# OutputBoard.net
KiCad netlist of a schematic drawn in EAGLE
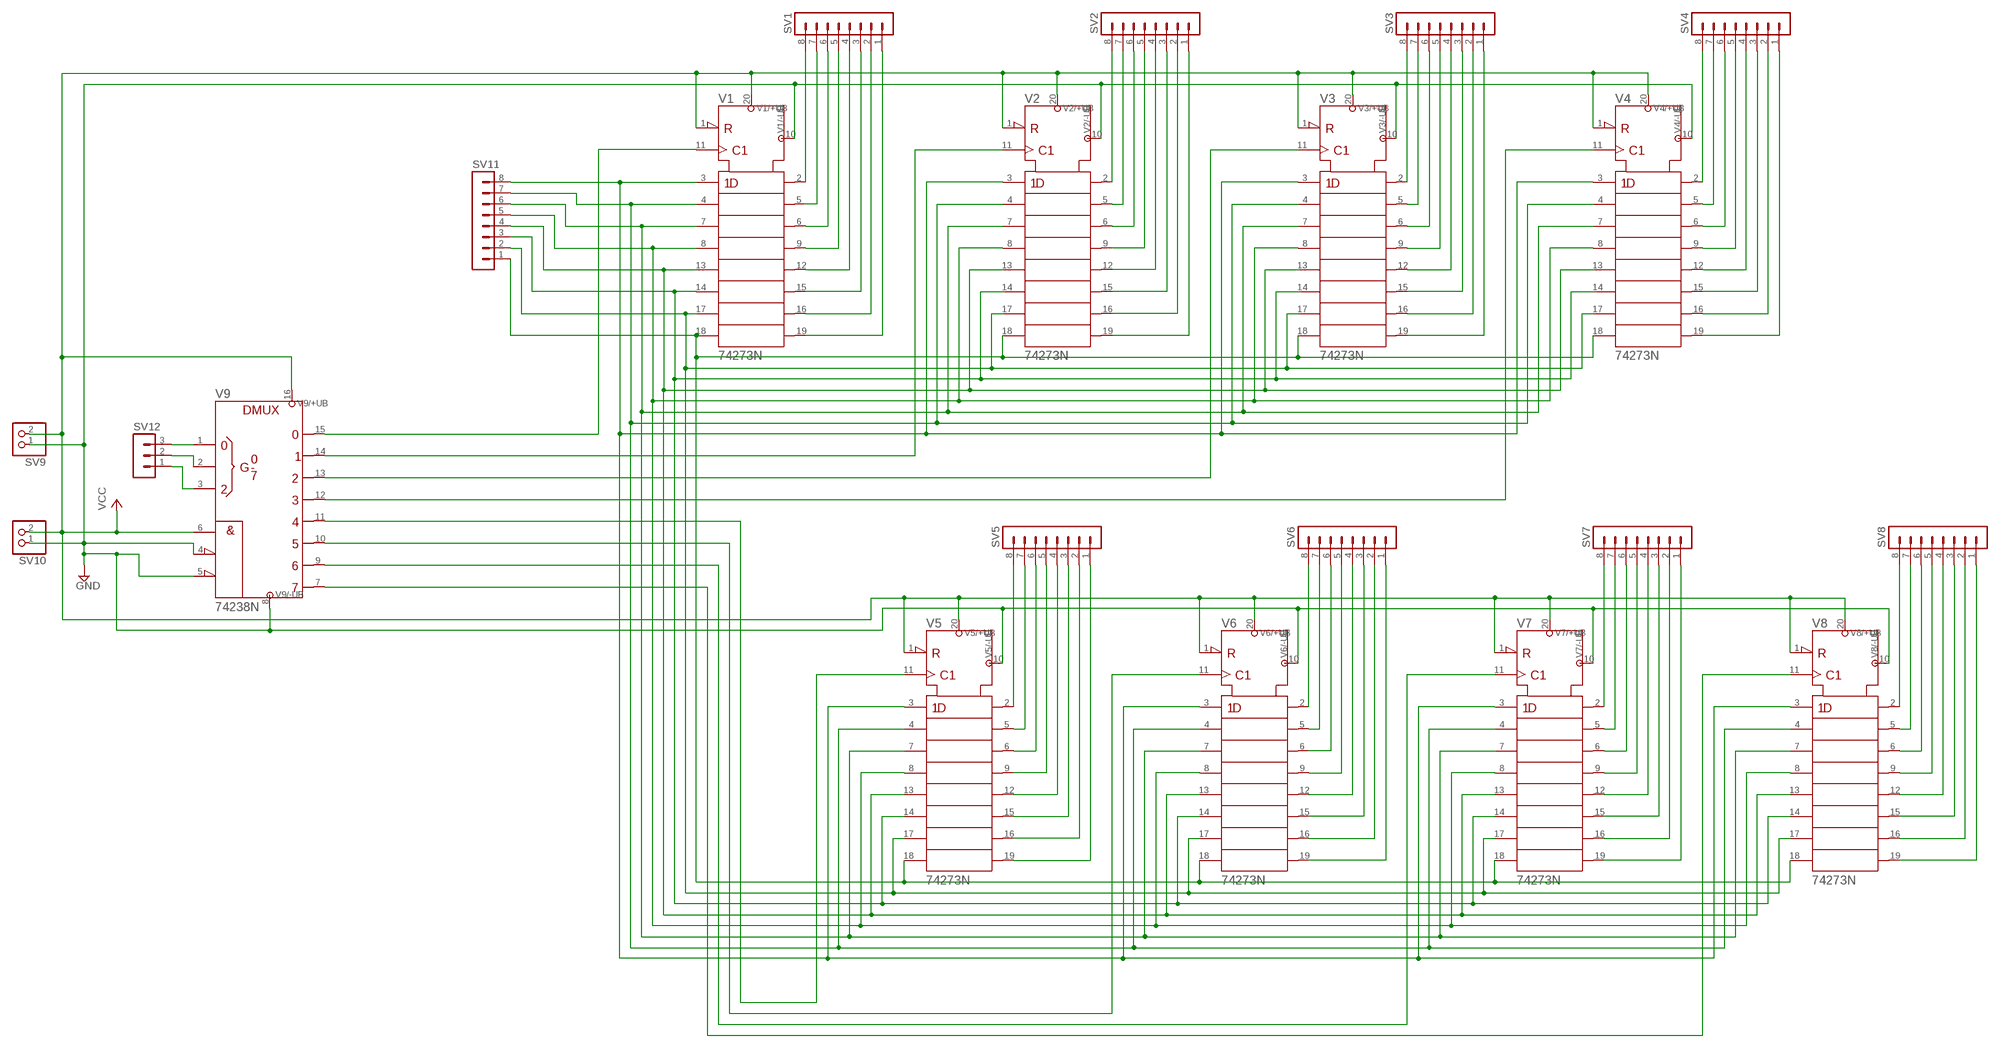
[diagram p0: schematic, sheet 1]

(export (version "E")
  (design (tool "Eeschema 10.0.6"))
  (components
    (comp (ref "SV1")
      (value "MA08-1")
      (footprint "eagle-import:MA08-1")
      (libsource (lib "eagle-import") (part "MA08-1"))
    )
    (comp (ref "SV2")
      (value "MA08-1")
      (footprint "eagle-import:MA08-1")
      (libsource (lib "eagle-import") (part "MA08-1"))
    )
    (comp (ref "SV3")
      (value "MA08-1")
      (footprint "eagle-import:MA08-1")
      (libsource (lib "eagle-import") (part "MA08-1"))
    )
    (comp (ref "SV4")
      (value "MA08-1")
      (footprint "eagle-import:MA08-1")
      (libsource (lib "eagle-import") (part "MA08-1"))
    )
    (comp (ref "SV5")
      (value "MA08-1")
      (footprint "eagle-import:MA08-1")
      (libsource (lib "eagle-import") (part "MA08-1"))
    )
    (comp (ref "SV6")
      (value "MA08-1")
      (footprint "eagle-import:MA08-1")
      (libsource (lib "eagle-import") (part "MA08-1"))
    )
    (comp (ref "SV7")
      (value "MA08-1")
      (footprint "eagle-import:MA08-1")
      (libsource (lib "eagle-import") (part "MA08-1"))
    )
    (comp (ref "SV8")
      (value "MA08-1")
      (footprint "eagle-import:MA08-1")
      (libsource (lib "eagle-import") (part "MA08-1"))
    )
    (comp (ref "SV9")
      (value "PINHD-1X2")
      (footprint "eagle-import:1X02")
      (libsource (lib "eagle-import") (part "PINHD-1X2"))
    )
    (comp (ref "SV10")
      (value "PINHD-1X2")
      (footprint "eagle-import:1X02")
      (libsource (lib "eagle-import") (part "PINHD-1X2"))
    )
    (comp (ref "SV11")
      (value "MA08-1")
      (footprint "eagle-import:MA08-1")
      (libsource (lib "eagle-import") (part "MA08-1"))
    )
    (comp (ref "SV12")
      (value "MA03-1")
      (footprint "eagle-import:MA03-1")
      (libsource (lib "eagle-import") (part "MA03-1"))
    )
    (comp (ref "V1")
      (value "74273N")
      (footprint "eagle-import:DIL20")
      (libsource (lib "eagle-import") (part "74273N"))
    )
    (comp (ref "V2")
      (value "74273N")
      (footprint "eagle-import:DIL20")
      (libsource (lib "eagle-import") (part "74273N"))
    )
    (comp (ref "V3")
      (value "74273N")
      (footprint "eagle-import:DIL20")
      (libsource (lib "eagle-import") (part "74273N"))
    )
    (comp (ref "V4")
      (value "74273N")
      (footprint "eagle-import:DIL20")
      (libsource (lib "eagle-import") (part "74273N"))
    )
    (comp (ref "V5")
      (value "74273N")
      (footprint "eagle-import:DIL20")
      (libsource (lib "eagle-import") (part "74273N"))
    )
    (comp (ref "V6")
      (value "74273N")
      (footprint "eagle-import:DIL20")
      (libsource (lib "eagle-import") (part "74273N"))
    )
    (comp (ref "V7")
      (value "74273N")
      (footprint "eagle-import:DIL20")
      (libsource (lib "eagle-import") (part "74273N"))
    )
    (comp (ref "V8")
      (value "74273N")
      (footprint "eagle-import:DIL20")
      (libsource (lib "eagle-import") (part "74273N"))
    )
    (comp (ref "V9")
      (value "74238N")
      (footprint "eagle-import:DIL16")
      (libsource (lib "eagle-import") (part "74238N"))
    )
  )
  (nets
    (net (code "1") (name "GND") (class "Default")
      (node (ref "SV10") (pin "1") (pinfunction "1_1") (pintype "passive"))
      (node (ref "SV9") (pin "1") (pinfunction "1_1") (pintype "passive"))
      (node (ref "V1") (pin "10") (pinfunction "-UB_10") (pintype "power_in"))
      (node (ref "V2") (pin "10") (pinfunction "-UB_10") (pintype "power_in"))
      (node (ref "V3") (pin "10") (pinfunction "-UB_10") (pintype "power_in"))
      (node (ref "V4") (pin "10") (pinfunction "-UB_10") (pintype "power_in"))
      (node (ref "V5") (pin "10") (pinfunction "-UB_10") (pintype "power_in"))
      (node (ref "V6") (pin "10") (pinfunction "-UB_10") (pintype "power_in"))
      (node (ref "V7") (pin "10") (pinfunction "-UB_10") (pintype "power_in"))
      (node (ref "V8") (pin "10") (pinfunction "-UB_10") (pintype "power_in"))
      (node (ref "V9") (pin "4") (pinfunction "~{G2A}_4") (pintype "input"))
      (node (ref "V9") (pin "5") (pinfunction "~{G2B}_5") (pintype "input"))
      (node (ref "V9") (pin "8") (pinfunction "-UB_8") (pintype "power_in"))
    )
    (net (code "2") (name "Net-(V1C-1D)") (class "Default")
      (node (ref "SV11") (pin "8") (pinfunction "8_8") (pintype "passive"))
      (node (ref "V1") (pin "3") (pinfunction "1D_3") (pintype "input"))
      (node (ref "V2") (pin "3") (pinfunction "1D_3") (pintype "input"))
      (node (ref "V3") (pin "3") (pinfunction "1D_3") (pintype "input"))
      (node (ref "V4") (pin "3") (pinfunction "1D_3") (pintype "input"))
      (node (ref "V5") (pin "3") (pinfunction "1D_3") (pintype "input"))
      (node (ref "V6") (pin "3") (pinfunction "1D_3") (pintype "input"))
      (node (ref "V7") (pin "3") (pinfunction "1D_3") (pintype "input"))
      (node (ref "V8") (pin "3") (pinfunction "1D_3") (pintype "input"))
    )
    (net (code "3") (name "Net-(V1C-1Q)") (class "Default")
      (node (ref "SV1") (pin "8") (pinfunction "8_8") (pintype "passive"))
      (node (ref "V1") (pin "2") (pinfunction "1Q_2") (pintype "output"))
    )
    (net (code "4") (name "Net-(V1C-2D)") (class "Default")
      (node (ref "SV11") (pin "7") (pinfunction "7_7") (pintype "passive"))
      (node (ref "V1") (pin "4") (pinfunction "2D_4") (pintype "input"))
      (node (ref "V2") (pin "4") (pinfunction "2D_4") (pintype "input"))
      (node (ref "V3") (pin "4") (pinfunction "2D_4") (pintype "input"))
      (node (ref "V4") (pin "4") (pinfunction "2D_4") (pintype "input"))
      (node (ref "V5") (pin "4") (pinfunction "2D_4") (pintype "input"))
      (node (ref "V6") (pin "4") (pinfunction "2D_4") (pintype "input"))
      (node (ref "V7") (pin "4") (pinfunction "2D_4") (pintype "input"))
      (node (ref "V8") (pin "4") (pinfunction "2D_4") (pintype "input"))
    )
    (net (code "5") (name "Net-(V1C-2Q)") (class "Default")
      (node (ref "SV1") (pin "7") (pinfunction "7_7") (pintype "passive"))
      (node (ref "V1") (pin "5") (pinfunction "2Q_5") (pintype "output"))
    )
    (net (code "6") (name "Net-(V1C-3D)") (class "Default")
      (node (ref "SV11") (pin "6") (pinfunction "6_6") (pintype "passive"))
      (node (ref "V1") (pin "7") (pinfunction "3D_7") (pintype "input"))
      (node (ref "V2") (pin "7") (pinfunction "3D_7") (pintype "input"))
      (node (ref "V3") (pin "7") (pinfunction "3D_7") (pintype "input"))
      (node (ref "V4") (pin "7") (pinfunction "3D_7") (pintype "input"))
      (node (ref "V5") (pin "7") (pinfunction "3D_7") (pintype "input"))
      (node (ref "V6") (pin "7") (pinfunction "3D_7") (pintype "input"))
      (node (ref "V7") (pin "7") (pinfunction "3D_7") (pintype "input"))
      (node (ref "V8") (pin "7") (pinfunction "3D_7") (pintype "input"))
    )
    (net (code "7") (name "Net-(V1C-3Q)") (class "Default")
      (node (ref "SV1") (pin "6") (pinfunction "6_6") (pintype "passive"))
      (node (ref "V1") (pin "6") (pinfunction "3Q_6") (pintype "output"))
    )
    (net (code "8") (name "Net-(V1C-4D)") (class "Default")
      (node (ref "SV11") (pin "5") (pinfunction "5_5") (pintype "passive"))
      (node (ref "V1") (pin "8") (pinfunction "4D_8") (pintype "input"))
      (node (ref "V2") (pin "8") (pinfunction "4D_8") (pintype "input"))
      (node (ref "V3") (pin "8") (pinfunction "4D_8") (pintype "input"))
      (node (ref "V4") (pin "8") (pinfunction "4D_8") (pintype "input"))
      (node (ref "V5") (pin "8") (pinfunction "4D_8") (pintype "input"))
      (node (ref "V6") (pin "8") (pinfunction "4D_8") (pintype "input"))
      (node (ref "V7") (pin "8") (pinfunction "4D_8") (pintype "input"))
      (node (ref "V8") (pin "8") (pinfunction "4D_8") (pintype "input"))
    )
    (net (code "9") (name "Net-(V1C-4Q)") (class "Default")
      (node (ref "SV1") (pin "5") (pinfunction "5_5") (pintype "passive"))
      (node (ref "V1") (pin "9") (pinfunction "4Q_9") (pintype "output"))
    )
    (net (code "10") (name "Net-(V1C-5D)") (class "Default")
      (node (ref "SV11") (pin "4") (pinfunction "4_4") (pintype "passive"))
      (node (ref "V1") (pin "13") (pinfunction "5D_13") (pintype "input"))
      (node (ref "V2") (pin "13") (pinfunction "5D_13") (pintype "input"))
      (node (ref "V3") (pin "13") (pinfunction "5D_13") (pintype "input"))
      (node (ref "V4") (pin "13") (pinfunction "5D_13") (pintype "input"))
      (node (ref "V5") (pin "13") (pinfunction "5D_13") (pintype "input"))
      (node (ref "V6") (pin "13") (pinfunction "5D_13") (pintype "input"))
      (node (ref "V7") (pin "13") (pinfunction "5D_13") (pintype "input"))
      (node (ref "V8") (pin "13") (pinfunction "5D_13") (pintype "input"))
    )
    (net (code "11") (name "Net-(V1C-5Q)") (class "Default")
      (node (ref "SV1") (pin "4") (pinfunction "4_4") (pintype "passive"))
      (node (ref "V1") (pin "12") (pinfunction "5Q_12") (pintype "output"))
    )
    (net (code "12") (name "Net-(V1C-6D)") (class "Default")
      (node (ref "SV11") (pin "3") (pinfunction "3_3") (pintype "passive"))
      (node (ref "V1") (pin "14") (pinfunction "6D_14") (pintype "input"))
      (node (ref "V2") (pin "14") (pinfunction "6D_14") (pintype "input"))
      (node (ref "V3") (pin "14") (pinfunction "6D_14") (pintype "input"))
      (node (ref "V4") (pin "14") (pinfunction "6D_14") (pintype "input"))
      (node (ref "V5") (pin "14") (pinfunction "6D_14") (pintype "input"))
      (node (ref "V6") (pin "14") (pinfunction "6D_14") (pintype "input"))
      (node (ref "V7") (pin "14") (pinfunction "6D_14") (pintype "input"))
      (node (ref "V8") (pin "14") (pinfunction "6D_14") (pintype "input"))
    )
    (net (code "13") (name "Net-(V1C-6Q)") (class "Default")
      (node (ref "SV1") (pin "3") (pinfunction "3_3") (pintype "passive"))
      (node (ref "V1") (pin "15") (pinfunction "6Q_15") (pintype "output"))
    )
    (net (code "14") (name "Net-(V1C-7D)") (class "Default")
      (node (ref "SV11") (pin "2") (pinfunction "2_2") (pintype "passive"))
      (node (ref "V1") (pin "17") (pinfunction "7D_17") (pintype "input"))
      (node (ref "V2") (pin "17") (pinfunction "7D_17") (pintype "input"))
      (node (ref "V3") (pin "17") (pinfunction "7D_17") (pintype "input"))
      (node (ref "V4") (pin "17") (pinfunction "7D_17") (pintype "input"))
      (node (ref "V5") (pin "17") (pinfunction "7D_17") (pintype "input"))
      (node (ref "V6") (pin "17") (pinfunction "7D_17") (pintype "input"))
      (node (ref "V7") (pin "17") (pinfunction "7D_17") (pintype "input"))
      (node (ref "V8") (pin "17") (pinfunction "7D_17") (pintype "input"))
    )
    (net (code "15") (name "Net-(V1C-7Q)") (class "Default")
      (node (ref "SV1") (pin "2") (pinfunction "2_2") (pintype "passive"))
      (node (ref "V1") (pin "16") (pinfunction "7Q_16") (pintype "output"))
    )
    (net (code "16") (name "Net-(V1C-8D)") (class "Default")
      (node (ref "SV11") (pin "1") (pinfunction "1_1") (pintype "passive"))
      (node (ref "V1") (pin "18") (pinfunction "8D_18") (pintype "input"))
      (node (ref "V2") (pin "18") (pinfunction "8D_18") (pintype "input"))
      (node (ref "V3") (pin "18") (pinfunction "8D_18") (pintype "input"))
      (node (ref "V4") (pin "18") (pinfunction "8D_18") (pintype "input"))
      (node (ref "V5") (pin "18") (pinfunction "8D_18") (pintype "input"))
      (node (ref "V6") (pin "18") (pinfunction "8D_18") (pintype "input"))
      (node (ref "V7") (pin "18") (pinfunction "8D_18") (pintype "input"))
      (node (ref "V8") (pin "18") (pinfunction "8D_18") (pintype "input"))
    )
    (net (code "17") (name "Net-(V1C-8Q)") (class "Default")
      (node (ref "SV1") (pin "1") (pinfunction "1_1") (pintype "passive"))
      (node (ref "V1") (pin "19") (pinfunction "8Q_19") (pintype "output"))
    )
    (net (code "18") (name "Net-(V1C-CLK)") (class "Default")
      (node (ref "V1") (pin "11") (pinfunction "CLK_11") (pintype "input"))
      (node (ref "V9") (pin "15") (pinfunction "Y0_15") (pintype "output"))
    )
    (net (code "19") (name "Net-(V2C-1Q)") (class "Default")
      (node (ref "SV2") (pin "8") (pinfunction "8_8") (pintype "passive"))
      (node (ref "V2") (pin "2") (pinfunction "1Q_2") (pintype "output"))
    )
    (net (code "20") (name "Net-(V2C-2Q)") (class "Default")
      (node (ref "SV2") (pin "7") (pinfunction "7_7") (pintype "passive"))
      (node (ref "V2") (pin "5") (pinfunction "2Q_5") (pintype "output"))
    )
    (net (code "21") (name "Net-(V2C-3Q)") (class "Default")
      (node (ref "SV2") (pin "6") (pinfunction "6_6") (pintype "passive"))
      (node (ref "V2") (pin "6") (pinfunction "3Q_6") (pintype "output"))
    )
    (net (code "22") (name "Net-(V2C-4Q)") (class "Default")
      (node (ref "SV2") (pin "5") (pinfunction "5_5") (pintype "passive"))
      (node (ref "V2") (pin "9") (pinfunction "4Q_9") (pintype "output"))
    )
    (net (code "23") (name "Net-(V2C-5Q)") (class "Default")
      (node (ref "SV2") (pin "4") (pinfunction "4_4") (pintype "passive"))
      (node (ref "V2") (pin "12") (pinfunction "5Q_12") (pintype "output"))
    )
    (net (code "24") (name "Net-(V2C-6Q)") (class "Default")
      (node (ref "SV2") (pin "3") (pinfunction "3_3") (pintype "passive"))
      (node (ref "V2") (pin "15") (pinfunction "6Q_15") (pintype "output"))
    )
    (net (code "25") (name "Net-(V2C-7Q)") (class "Default")
      (node (ref "SV2") (pin "2") (pinfunction "2_2") (pintype "passive"))
      (node (ref "V2") (pin "16") (pinfunction "7Q_16") (pintype "output"))
    )
    (net (code "26") (name "Net-(V2C-8Q)") (class "Default")
      (node (ref "SV2") (pin "1") (pinfunction "1_1") (pintype "passive"))
      (node (ref "V2") (pin "19") (pinfunction "8Q_19") (pintype "output"))
    )
    (net (code "27") (name "Net-(V2C-CLK)") (class "Default")
      (node (ref "V2") (pin "11") (pinfunction "CLK_11") (pintype "input"))
      (node (ref "V9") (pin "14") (pinfunction "Y1_14") (pintype "output"))
    )
    (net (code "28") (name "Net-(V3C-1Q)") (class "Default")
      (node (ref "SV3") (pin "8") (pinfunction "8_8") (pintype "passive"))
      (node (ref "V3") (pin "2") (pinfunction "1Q_2") (pintype "output"))
    )
    (net (code "29") (name "Net-(V3C-2Q)") (class "Default")
      (node (ref "SV3") (pin "7") (pinfunction "7_7") (pintype "passive"))
      (node (ref "V3") (pin "5") (pinfunction "2Q_5") (pintype "output"))
    )
    (net (code "30") (name "Net-(V3C-3Q)") (class "Default")
      (node (ref "SV3") (pin "6") (pinfunction "6_6") (pintype "passive"))
      (node (ref "V3") (pin "6") (pinfunction "3Q_6") (pintype "output"))
    )
    (net (code "31") (name "Net-(V3C-4Q)") (class "Default")
      (node (ref "SV3") (pin "5") (pinfunction "5_5") (pintype "passive"))
      (node (ref "V3") (pin "9") (pinfunction "4Q_9") (pintype "output"))
    )
    (net (code "32") (name "Net-(V3C-5Q)") (class "Default")
      (node (ref "SV3") (pin "4") (pinfunction "4_4") (pintype "passive"))
      (node (ref "V3") (pin "12") (pinfunction "5Q_12") (pintype "output"))
    )
    (net (code "33") (name "Net-(V3C-6Q)") (class "Default")
      (node (ref "SV3") (pin "3") (pinfunction "3_3") (pintype "passive"))
      (node (ref "V3") (pin "15") (pinfunction "6Q_15") (pintype "output"))
    )
    (net (code "34") (name "Net-(V3C-7Q)") (class "Default")
      (node (ref "SV3") (pin "2") (pinfunction "2_2") (pintype "passive"))
      (node (ref "V3") (pin "16") (pinfunction "7Q_16") (pintype "output"))
    )
    (net (code "35") (name "Net-(V3C-8Q)") (class "Default")
      (node (ref "SV3") (pin "1") (pinfunction "1_1") (pintype "passive"))
      (node (ref "V3") (pin "19") (pinfunction "8Q_19") (pintype "output"))
    )
    (net (code "36") (name "Net-(V3C-CLK)") (class "Default")
      (node (ref "V3") (pin "11") (pinfunction "CLK_11") (pintype "input"))
      (node (ref "V9") (pin "13") (pinfunction "Y2_13") (pintype "output"))
    )
    (net (code "37") (name "Net-(V4C-1Q)") (class "Default")
      (node (ref "SV4") (pin "8") (pinfunction "8_8") (pintype "passive"))
      (node (ref "V4") (pin "2") (pinfunction "1Q_2") (pintype "output"))
    )
    (net (code "38") (name "Net-(V4C-2Q)") (class "Default")
      (node (ref "SV4") (pin "7") (pinfunction "7_7") (pintype "passive"))
      (node (ref "V4") (pin "5") (pinfunction "2Q_5") (pintype "output"))
    )
    (net (code "39") (name "Net-(V4C-3Q)") (class "Default")
      (node (ref "SV4") (pin "6") (pinfunction "6_6") (pintype "passive"))
      (node (ref "V4") (pin "6") (pinfunction "3Q_6") (pintype "output"))
    )
    (net (code "40") (name "Net-(V4C-4Q)") (class "Default")
      (node (ref "SV4") (pin "5") (pinfunction "5_5") (pintype "passive"))
      (node (ref "V4") (pin "9") (pinfunction "4Q_9") (pintype "output"))
    )
    (net (code "41") (name "Net-(V4C-5Q)") (class "Default")
      (node (ref "SV4") (pin "4") (pinfunction "4_4") (pintype "passive"))
      (node (ref "V4") (pin "12") (pinfunction "5Q_12") (pintype "output"))
    )
    (net (code "42") (name "Net-(V4C-6Q)") (class "Default")
      (node (ref "SV4") (pin "3") (pinfunction "3_3") (pintype "passive"))
      (node (ref "V4") (pin "15") (pinfunction "6Q_15") (pintype "output"))
    )
    (net (code "43") (name "Net-(V4C-7Q)") (class "Default")
      (node (ref "SV4") (pin "2") (pinfunction "2_2") (pintype "passive"))
      (node (ref "V4") (pin "16") (pinfunction "7Q_16") (pintype "output"))
    )
    (net (code "44") (name "Net-(V4C-8Q)") (class "Default")
      (node (ref "SV4") (pin "1") (pinfunction "1_1") (pintype "passive"))
      (node (ref "V4") (pin "19") (pinfunction "8Q_19") (pintype "output"))
    )
    (net (code "45") (name "Net-(V4C-CLK)") (class "Default")
      (node (ref "V4") (pin "11") (pinfunction "CLK_11") (pintype "input"))
      (node (ref "V9") (pin "12") (pinfunction "Y3_12") (pintype "output"))
    )
    (net (code "46") (name "Net-(V5C-1Q)") (class "Default")
      (node (ref "SV5") (pin "8") (pinfunction "8_8") (pintype "passive"))
      (node (ref "V5") (pin "2") (pinfunction "1Q_2") (pintype "output"))
    )
    (net (code "47") (name "Net-(V5C-2Q)") (class "Default")
      (node (ref "SV5") (pin "7") (pinfunction "7_7") (pintype "passive"))
      (node (ref "V5") (pin "5") (pinfunction "2Q_5") (pintype "output"))
    )
    (net (code "48") (name "Net-(V5C-3Q)") (class "Default")
      (node (ref "SV5") (pin "6") (pinfunction "6_6") (pintype "passive"))
      (node (ref "V5") (pin "6") (pinfunction "3Q_6") (pintype "output"))
    )
    (net (code "49") (name "Net-(V5C-4Q)") (class "Default")
      (node (ref "SV5") (pin "5") (pinfunction "5_5") (pintype "passive"))
      (node (ref "V5") (pin "9") (pinfunction "4Q_9") (pintype "output"))
    )
    (net (code "50") (name "Net-(V5C-5Q)") (class "Default")
      (node (ref "SV5") (pin "4") (pinfunction "4_4") (pintype "passive"))
      (node (ref "V5") (pin "12") (pinfunction "5Q_12") (pintype "output"))
    )
    (net (code "51") (name "Net-(V5C-6Q)") (class "Default")
      (node (ref "SV5") (pin "3") (pinfunction "3_3") (pintype "passive"))
      (node (ref "V5") (pin "15") (pinfunction "6Q_15") (pintype "output"))
    )
    (net (code "52") (name "Net-(V5C-7Q)") (class "Default")
      (node (ref "SV5") (pin "2") (pinfunction "2_2") (pintype "passive"))
      (node (ref "V5") (pin "16") (pinfunction "7Q_16") (pintype "output"))
    )
    (net (code "53") (name "Net-(V5C-8Q)") (class "Default")
      (node (ref "SV5") (pin "1") (pinfunction "1_1") (pintype "passive"))
      (node (ref "V5") (pin "19") (pinfunction "8Q_19") (pintype "output"))
    )
    (net (code "54") (name "Net-(V5C-CLK)") (class "Default")
      (node (ref "V5") (pin "11") (pinfunction "CLK_11") (pintype "input"))
      (node (ref "V9") (pin "11") (pinfunction "Y4_11") (pintype "output"))
    )
    (net (code "55") (name "Net-(V6C-1Q)") (class "Default")
      (node (ref "SV6") (pin "8") (pinfunction "8_8") (pintype "passive"))
      (node (ref "V6") (pin "2") (pinfunction "1Q_2") (pintype "output"))
    )
    (net (code "56") (name "Net-(V6C-2Q)") (class "Default")
      (node (ref "SV6") (pin "7") (pinfunction "7_7") (pintype "passive"))
      (node (ref "V6") (pin "5") (pinfunction "2Q_5") (pintype "output"))
    )
    (net (code "57") (name "Net-(V6C-3Q)") (class "Default")
      (node (ref "SV6") (pin "6") (pinfunction "6_6") (pintype "passive"))
      (node (ref "V6") (pin "6") (pinfunction "3Q_6") (pintype "output"))
    )
    (net (code "58") (name "Net-(V6C-4Q)") (class "Default")
      (node (ref "SV6") (pin "5") (pinfunction "5_5") (pintype "passive"))
      (node (ref "V6") (pin "9") (pinfunction "4Q_9") (pintype "output"))
    )
    (net (code "59") (name "Net-(V6C-5Q)") (class "Default")
      (node (ref "SV6") (pin "4") (pinfunction "4_4") (pintype "passive"))
      (node (ref "V6") (pin "12") (pinfunction "5Q_12") (pintype "output"))
    )
    (net (code "60") (name "Net-(V6C-6Q)") (class "Default")
      (node (ref "SV6") (pin "3") (pinfunction "3_3") (pintype "passive"))
      (node (ref "V6") (pin "15") (pinfunction "6Q_15") (pintype "output"))
    )
    (net (code "61") (name "Net-(V6C-7Q)") (class "Default")
      (node (ref "SV6") (pin "2") (pinfunction "2_2") (pintype "passive"))
      (node (ref "V6") (pin "16") (pinfunction "7Q_16") (pintype "output"))
    )
    (net (code "62") (name "Net-(V6C-8Q)") (class "Default")
      (node (ref "SV6") (pin "1") (pinfunction "1_1") (pintype "passive"))
      (node (ref "V6") (pin "19") (pinfunction "8Q_19") (pintype "output"))
    )
    (net (code "63") (name "Net-(V6C-CLK)") (class "Default")
      (node (ref "V6") (pin "11") (pinfunction "CLK_11") (pintype "input"))
      (node (ref "V9") (pin "10") (pinfunction "Y5_10") (pintype "output"))
    )
    (net (code "64") (name "Net-(V7C-1Q)") (class "Default")
      (node (ref "SV7") (pin "8") (pinfunction "8_8") (pintype "passive"))
      (node (ref "V7") (pin "2") (pinfunction "1Q_2") (pintype "output"))
    )
    (net (code "65") (name "Net-(V7C-2Q)") (class "Default")
      (node (ref "SV7") (pin "7") (pinfunction "7_7") (pintype "passive"))
      (node (ref "V7") (pin "5") (pinfunction "2Q_5") (pintype "output"))
    )
    (net (code "66") (name "Net-(V7C-3Q)") (class "Default")
      (node (ref "SV7") (pin "6") (pinfunction "6_6") (pintype "passive"))
      (node (ref "V7") (pin "6") (pinfunction "3Q_6") (pintype "output"))
    )
    (net (code "67") (name "Net-(V7C-4Q)") (class "Default")
      (node (ref "SV7") (pin "5") (pinfunction "5_5") (pintype "passive"))
      (node (ref "V7") (pin "9") (pinfunction "4Q_9") (pintype "output"))
    )
    (net (code "68") (name "Net-(V7C-5Q)") (class "Default")
      (node (ref "SV7") (pin "4") (pinfunction "4_4") (pintype "passive"))
      (node (ref "V7") (pin "12") (pinfunction "5Q_12") (pintype "output"))
    )
    (net (code "69") (name "Net-(V7C-6Q)") (class "Default")
      (node (ref "SV7") (pin "3") (pinfunction "3_3") (pintype "passive"))
      (node (ref "V7") (pin "15") (pinfunction "6Q_15") (pintype "output"))
    )
    (net (code "70") (name "Net-(V7C-7Q)") (class "Default")
      (node (ref "SV7") (pin "2") (pinfunction "2_2") (pintype "passive"))
      (node (ref "V7") (pin "16") (pinfunction "7Q_16") (pintype "output"))
    )
    (net (code "71") (name "Net-(V7C-8Q)") (class "Default")
      (node (ref "SV7") (pin "1") (pinfunction "1_1") (pintype "passive"))
      (node (ref "V7") (pin "19") (pinfunction "8Q_19") (pintype "output"))
    )
    (net (code "72") (name "Net-(V7C-CLK)") (class "Default")
      (node (ref "V7") (pin "11") (pinfunction "CLK_11") (pintype "input"))
      (node (ref "V9") (pin "9") (pinfunction "Y6_9") (pintype "output"))
    )
    (net (code "73") (name "Net-(V8C-1Q)") (class "Default")
      (node (ref "SV8") (pin "8") (pinfunction "8_8") (pintype "passive"))
      (node (ref "V8") (pin "2") (pinfunction "1Q_2") (pintype "output"))
    )
    (net (code "74") (name "Net-(V8C-2Q)") (class "Default")
      (node (ref "SV8") (pin "7") (pinfunction "7_7") (pintype "passive"))
      (node (ref "V8") (pin "5") (pinfunction "2Q_5") (pintype "output"))
    )
    (net (code "75") (name "Net-(V8C-3Q)") (class "Default")
      (node (ref "SV8") (pin "6") (pinfunction "6_6") (pintype "passive"))
      (node (ref "V8") (pin "6") (pinfunction "3Q_6") (pintype "output"))
    )
    (net (code "76") (name "Net-(V8C-4Q)") (class "Default")
      (node (ref "SV8") (pin "5") (pinfunction "5_5") (pintype "passive"))
      (node (ref "V8") (pin "9") (pinfunction "4Q_9") (pintype "output"))
    )
    (net (code "77") (name "Net-(V8C-5Q)") (class "Default")
      (node (ref "SV8") (pin "4") (pinfunction "4_4") (pintype "passive"))
      (node (ref "V8") (pin "12") (pinfunction "5Q_12") (pintype "output"))
    )
    (net (code "78") (name "Net-(V8C-6Q)") (class "Default")
      (node (ref "SV8") (pin "3") (pinfunction "3_3") (pintype "passive"))
      (node (ref "V8") (pin "15") (pinfunction "6Q_15") (pintype "output"))
    )
    (net (code "79") (name "Net-(V8C-7Q)") (class "Default")
      (node (ref "SV8") (pin "2") (pinfunction "2_2") (pintype "passive"))
      (node (ref "V8") (pin "16") (pinfunction "7Q_16") (pintype "output"))
    )
    (net (code "80") (name "Net-(V8C-8Q)") (class "Default")
      (node (ref "SV8") (pin "1") (pinfunction "1_1") (pintype "passive"))
      (node (ref "V8") (pin "19") (pinfunction "8Q_19") (pintype "output"))
    )
    (net (code "81") (name "Net-(V8C-CLK)") (class "Default")
      (node (ref "V8") (pin "11") (pinfunction "CLK_11") (pintype "input"))
      (node (ref "V9") (pin "7") (pinfunction "Y7_7") (pintype "output"))
    )
    (net (code "82") (name "Net-(V9C-A)") (class "Default")
      (node (ref "SV12") (pin "3") (pinfunction "3_3") (pintype "passive"))
      (node (ref "V9") (pin "1") (pinfunction "A_1") (pintype "input"))
    )
    (net (code "83") (name "Net-(V9C-B)") (class "Default")
      (node (ref "SV12") (pin "2") (pinfunction "2_2") (pintype "passive"))
      (node (ref "V9") (pin "2") (pinfunction "B_2") (pintype "input"))
    )
    (net (code "84") (name "Net-(V9C-C)") (class "Default")
      (node (ref "SV12") (pin "1") (pinfunction "1_1") (pintype "passive"))
      (node (ref "V9") (pin "3") (pinfunction "C_3") (pintype "input"))
    )
    (net (code "85") (name "VCC") (class "Default")
      (node (ref "SV10") (pin "2") (pinfunction "2_2") (pintype "passive"))
      (node (ref "SV9") (pin "2") (pinfunction "2_2") (pintype "passive"))
      (node (ref "V1") (pin "1") (pinfunction "~{CLR}_1") (pintype "input"))
      (node (ref "V1") (pin "20") (pinfunction "+UB_20") (pintype "power_in"))
      (node (ref "V2") (pin "1") (pinfunction "~{CLR}_1") (pintype "input"))
      (node (ref "V2") (pin "20") (pinfunction "+UB_20") (pintype "power_in"))
      (node (ref "V3") (pin "1") (pinfunction "~{CLR}_1") (pintype "input"))
      (node (ref "V3") (pin "20") (pinfunction "+UB_20") (pintype "power_in"))
      (node (ref "V4") (pin "1") (pinfunction "~{CLR}_1") (pintype "input"))
      (node (ref "V4") (pin "20") (pinfunction "+UB_20") (pintype "power_in"))
      (node (ref "V5") (pin "1") (pinfunction "~{CLR}_1") (pintype "input"))
      (node (ref "V5") (pin "20") (pinfunction "+UB_20") (pintype "power_in"))
      (node (ref "V6") (pin "1") (pinfunction "~{CLR}_1") (pintype "input"))
      (node (ref "V6") (pin "20") (pinfunction "+UB_20") (pintype "power_in"))
      (node (ref "V7") (pin "1") (pinfunction "~{CLR}_1") (pintype "input"))
      (node (ref "V7") (pin "20") (pinfunction "+UB_20") (pintype "power_in"))
      (node (ref "V8") (pin "1") (pinfunction "~{CLR}_1") (pintype "input"))
      (node (ref "V8") (pin "20") (pinfunction "+UB_20") (pintype "power_in"))
      (node (ref "V9") (pin "16") (pinfunction "+UB_16") (pintype "power_in"))
      (node (ref "V9") (pin "6") (pinfunction "G1_6") (pintype "input"))
    )
  )
)
